# ATtiny84.net
KiCad netlist of a schematic drawn in EAGLE
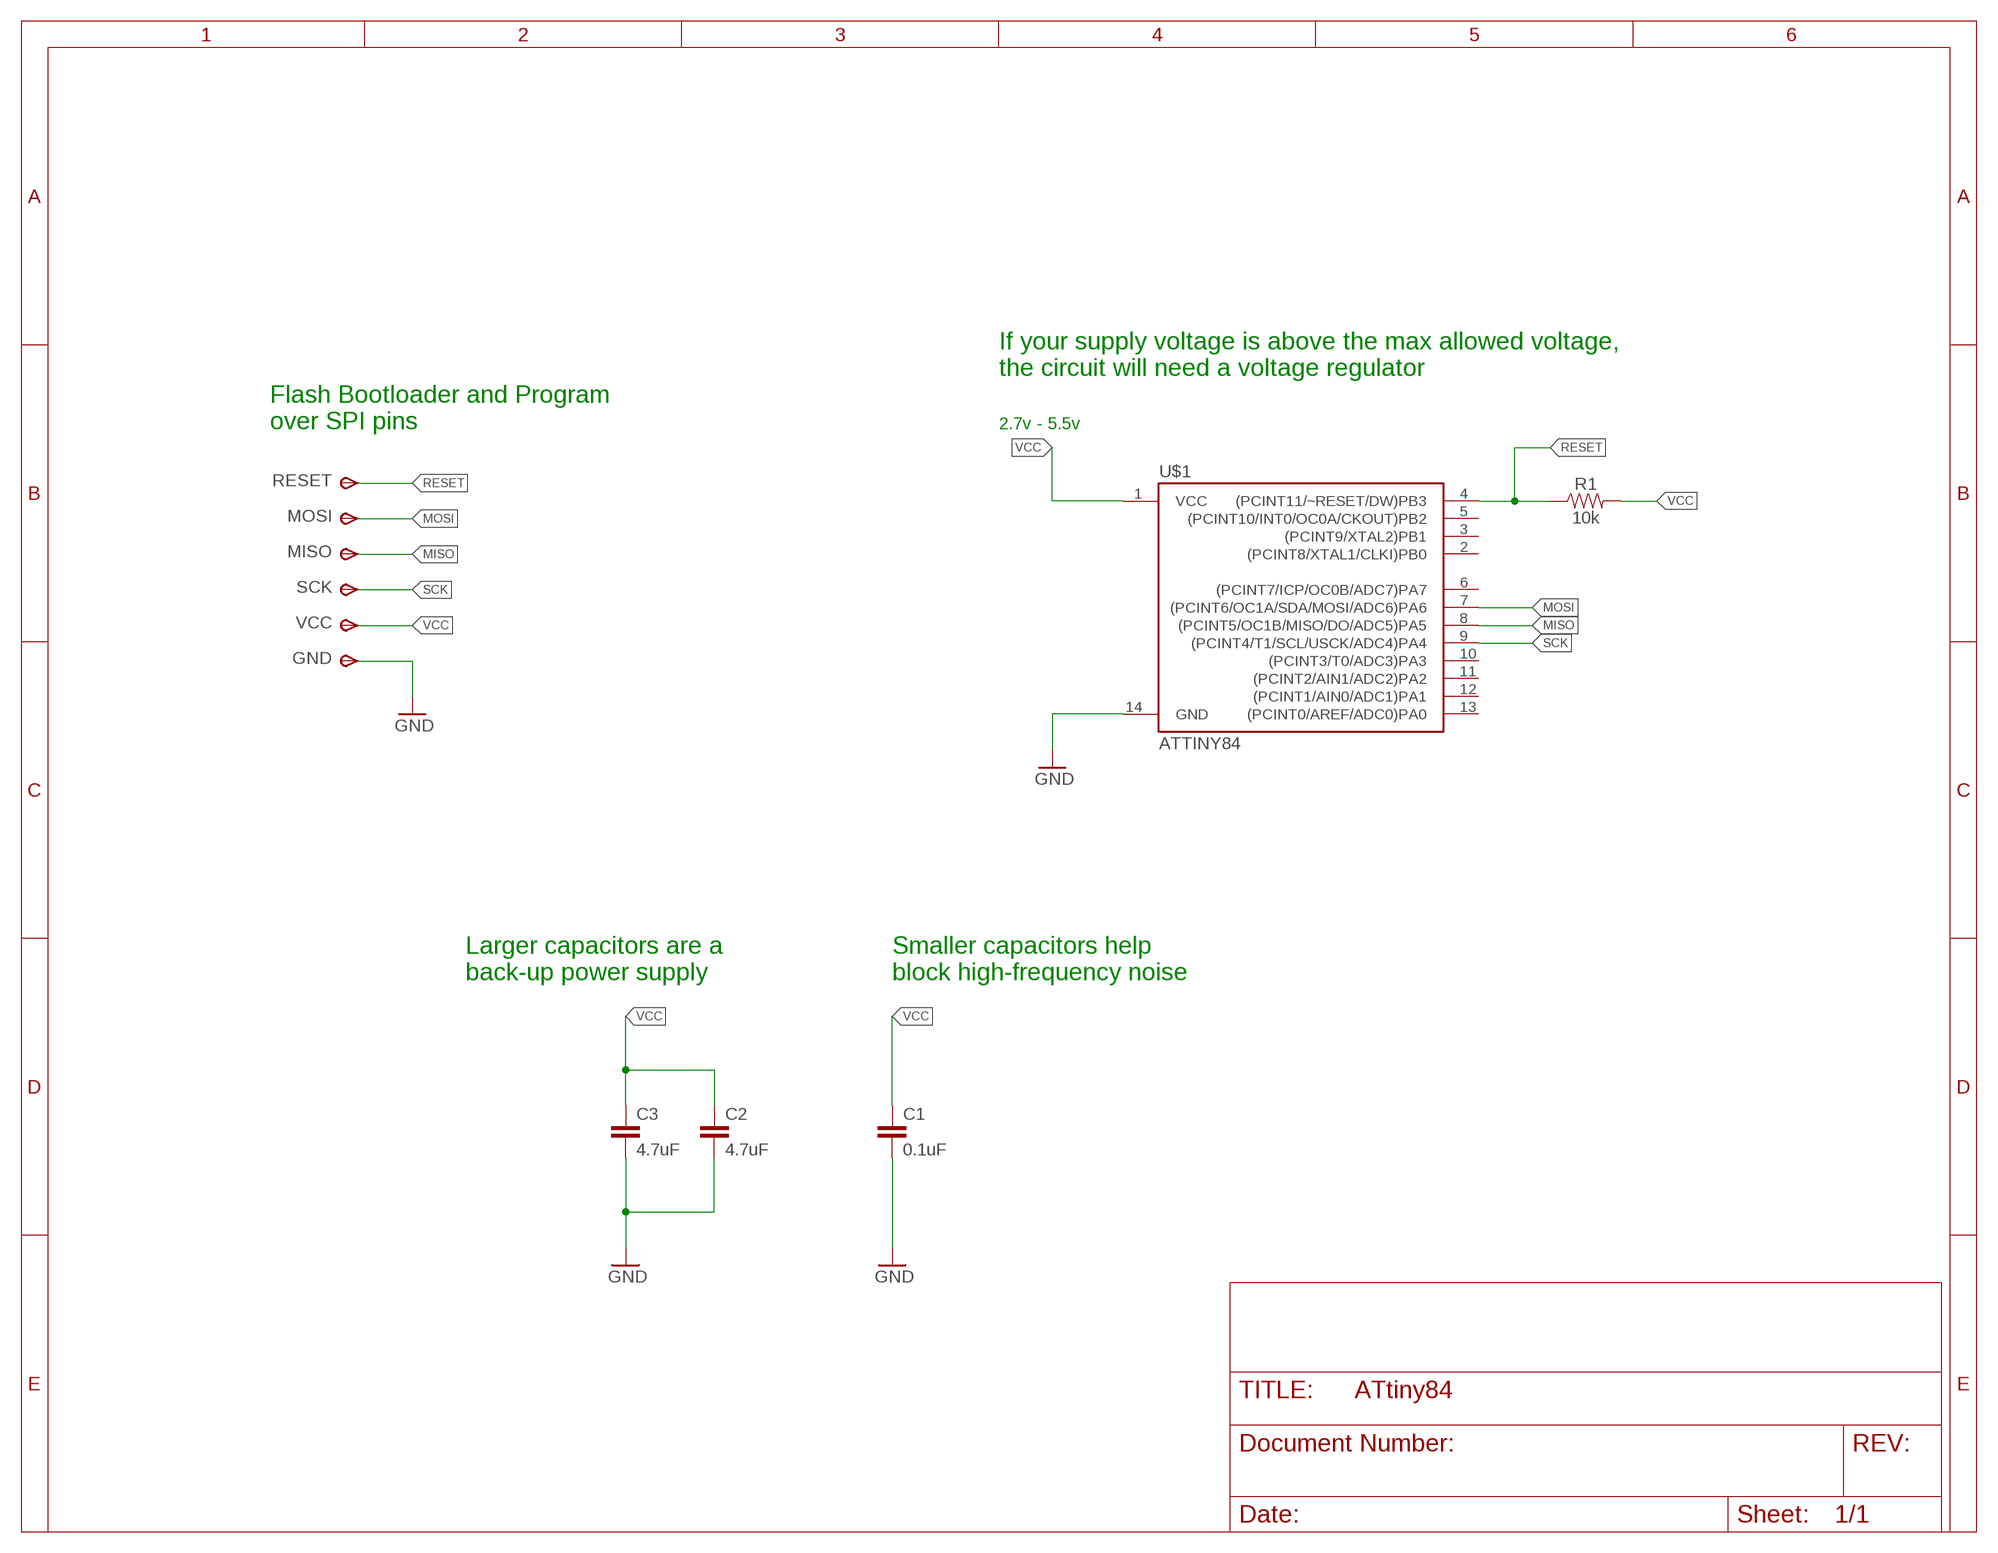
[diagram p0: schematic, sheet 1]

(export (version "E")
  (design (tool "Eeschema 10.0.6"))
  (components
    (comp (ref "C1")
      (value "0.1uF")
      (footprint "eagle-import:0603")
      (libsource (lib "eagle-import") (part "0.1UF-0603-25V-5%"))
    )
    (comp (ref "C2")
      (value "4.7uF")
      (footprint "eagle-import:0603")
      (libsource (lib "eagle-import") (part "4.7UF0603"))
    )
    (comp (ref "C3")
      (value "4.7uF")
      (footprint "eagle-import:0603")
      (libsource (lib "eagle-import") (part "4.7UF0603"))
    )
    (comp (ref "GND")
      (value "TPSTP14SQ")
      (footprint "eagle-import:TP14SQ")
      (libsource (lib "eagle-import") (part "TPSTP14SQ"))
    )
    (comp (ref "MISO")
      (value "TPSTP14SQ")
      (footprint "eagle-import:TP14SQ")
      (libsource (lib "eagle-import") (part "TPSTP14SQ"))
    )
    (comp (ref "MOSI")
      (value "TPSTP14SQ")
      (footprint "eagle-import:TP14SQ")
      (libsource (lib "eagle-import") (part "TPSTP14SQ"))
    )
    (comp (ref "R1")
      (value "10k")
      (footprint "eagle-import:0603")
      (libsource (lib "eagle-import") (part "10KOHM-0603-1/10W-1%"))
    )
    (comp (ref "RESET")
      (value "TPSTP14SQ")
      (footprint "eagle-import:TP14SQ")
      (libsource (lib "eagle-import") (part "TPSTP14SQ"))
    )
    (comp (ref "SCK")
      (value "TPSTP14SQ")
      (footprint "eagle-import:TP14SQ")
      (libsource (lib "eagle-import") (part "TPSTP14SQ"))
    )
    (comp (ref "U$1")
      (value "ATTINY84")
      (footprint "eagle-import:SO14")
      (libsource (lib "eagle-import") (part "ATTINY84"))
    )
    (comp (ref "VCC")
      (value "TPSTP14SQ")
      (footprint "eagle-import:TP14SQ")
      (libsource (lib "eagle-import") (part "TPSTP14SQ"))
    )
  )
  (nets
    (net (code "1") (name "GND") (class "Default")
      (node (ref "C1") (pin "2") (pinfunction "2_2") (pintype "passive"))
      (node (ref "C2") (pin "2") (pinfunction "2_2") (pintype "passive"))
      (node (ref "C3") (pin "2") (pinfunction "2_2") (pintype "passive"))
      (node (ref "GND") (pin "TP") (pinfunction "PP_TP") (pintype "input"))
      (node (ref "U$1") (pin "14") (pinfunction "GND_14") (pintype "bidirectional"))
    )
    (net (code "2") (name "MISO") (class "Default")
      (node (ref "MISO") (pin "TP") (pinfunction "PP_TP") (pintype "input"))
      (node (ref "U$1") (pin "8") (pinfunction "(PCINT5/OC1B/MISO/DO/ADC5)PA5_8") (pintype "bidirectional"))
    )
    (net (code "3") (name "MOSI") (class "Default")
      (node (ref "MOSI") (pin "TP") (pinfunction "PP_TP") (pintype "input"))
      (node (ref "U$1") (pin "7") (pinfunction "(PCINT6/OC1A/SDA/MOSI/ADC6)PA6_7") (pintype "bidirectional"))
    )
    (net (code "4") (name "RESET") (class "Default")
      (node (ref "R1") (pin "1") (pinfunction "1_1") (pintype "passive"))
      (node (ref "RESET") (pin "TP") (pinfunction "PP_TP") (pintype "input"))
      (node (ref "U$1") (pin "4") (pinfunction "(PCINT11/~{RESET/DW})PB3_4") (pintype "bidirectional"))
    )
    (net (code "5") (name "SCK") (class "Default")
      (node (ref "SCK") (pin "TP") (pinfunction "PP_TP") (pintype "input"))
      (node (ref "U$1") (pin "9") (pinfunction "(PCINT4/T1/SCL/USCK/ADC4)PA4_9") (pintype "bidirectional"))
    )
    (net (code "6") (name "VCC") (class "Default")
      (node (ref "C1") (pin "1") (pinfunction "1_1") (pintype "passive"))
      (node (ref "C2") (pin "1") (pinfunction "1_1") (pintype "passive"))
      (node (ref "C3") (pin "1") (pinfunction "1_1") (pintype "passive"))
      (node (ref "R1") (pin "2") (pinfunction "2_2") (pintype "passive"))
      (node (ref "U$1") (pin "1") (pinfunction "VCC_1") (pintype "bidirectional"))
      (node (ref "VCC") (pin "TP") (pinfunction "PP_TP") (pintype "input"))
    )
    (net (code "7") (name "unconnected-(U$1-(PCINT0{slash}AREF{slash}ADC0)PA0-Pad13)") (class "Default")
      (node (ref "U$1") (pin "13") (pinfunction "(PCINT0/AREF/ADC0)PA0_13") (pintype "bidirectional"))
    )
    (net (code "8") (name "unconnected-(U$1-(PCINT1{slash}AIN0{slash}ADC1)PA1-Pad12)") (class "Default")
      (node (ref "U$1") (pin "12") (pinfunction "(PCINT1/AIN0/ADC1)PA1_12") (pintype "bidirectional"))
    )
    (net (code "9") (name "unconnected-(U$1-(PCINT2{slash}AIN1{slash}ADC2)PA2-Pad11)") (class "Default")
      (node (ref "U$1") (pin "11") (pinfunction "(PCINT2/AIN1/ADC2)PA2_11") (pintype "bidirectional"))
    )
    (net (code "10") (name "unconnected-(U$1-(PCINT3{slash}T0{slash}ADC3)PA3-Pad10)") (class "Default")
      (node (ref "U$1") (pin "10") (pinfunction "(PCINT3/T0/ADC3)PA3_10") (pintype "bidirectional"))
    )
    (net (code "11") (name "unconnected-(U$1-(PCINT7{slash}ICP{slash}OC0B{slash}ADC7)PA7-Pad6)") (class "Default")
      (node (ref "U$1") (pin "6") (pinfunction "(PCINT7/ICP/OC0B/ADC7)PA7_6") (pintype "bidirectional"))
    )
    (net (code "12") (name "unconnected-(U$1-(PCINT8{slash}XTAL1{slash}CLKI)PB0-Pad2)") (class "Default")
      (node (ref "U$1") (pin "2") (pinfunction "(PCINT8/XTAL1/CLKI)PB0_2") (pintype "bidirectional"))
    )
    (net (code "13") (name "unconnected-(U$1-(PCINT9{slash}XTAL2)PB1-Pad3)") (class "Default")
      (node (ref "U$1") (pin "3") (pinfunction "(PCINT9/XTAL2)PB1_3") (pintype "bidirectional"))
    )
    (net (code "14") (name "unconnected-(U$1-(PCINT10{slash}INT0{slash}OC0A{slash}CKOUT)PB2-Pad5)") (class "Default")
      (node (ref "U$1") (pin "5") (pinfunction "(PCINT10/INT0/OC0A/CKOUT)PB2_5") (pintype "bidirectional"))
    )
  )
)
